# schematic.net
KiCad netlist of a schematic drawn in EAGLE
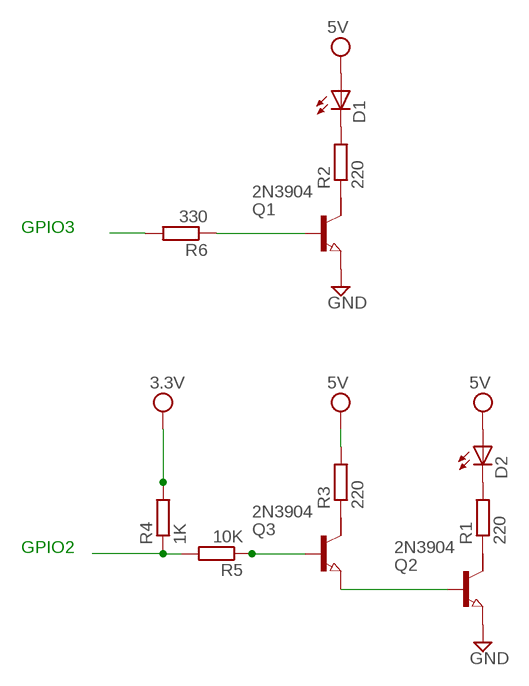
[diagram p0: schematic, sheet 1]

(export (version "E")
  (design (tool "Eeschema 10.0.6"))
  (components
    (comp (ref "D1")
      (value "LED")
      (footprint "eagle-import:SMARTLED-TTW")
      (libsource (lib "eagle-import") (part "LED"))
    )
    (comp (ref "D2")
      (value "LED")
      (footprint "eagle-import:SMARTLED-TTW")
      (libsource (lib "eagle-import") (part "LED"))
    )
    (comp (ref "Q1")
      (value "2N3904")
      (footprint "eagle-import:SOT89")
      (libsource (lib "eagle-import") (part "NPN-TRANSISTIOR-2COLSOT89"))
    )
    (comp (ref "Q2")
      (value "2N3904")
      (footprint "eagle-import:SOT89")
      (libsource (lib "eagle-import") (part "NPN-TRANSISTIOR-2COLSOT89"))
    )
    (comp (ref "Q3")
      (value "2N3904")
      (footprint "eagle-import:SOT89")
      (libsource (lib "eagle-import") (part "NPN-TRANSISTIOR-2COLSOT89"))
    )
    (comp (ref "R1")
      (value "220")
      (footprint "eagle-import:R0805")
      (libsource (lib "eagle-import") (part "R"))
    )
    (comp (ref "R2")
      (value "220")
      (footprint "eagle-import:R0805")
      (libsource (lib "eagle-import") (part "R"))
    )
    (comp (ref "R3")
      (value "220")
      (footprint "eagle-import:R0805")
      (libsource (lib "eagle-import") (part "R"))
    )
    (comp (ref "R4")
      (value "1K")
      (footprint "eagle-import:R0805")
      (libsource (lib "eagle-import") (part "R"))
    )
    (comp (ref "R5")
      (value "10K")
      (footprint "eagle-import:R0805")
      (libsource (lib "eagle-import") (part "R"))
    )
    (comp (ref "R6")
      (value "330")
      (footprint "eagle-import:R0805")
      (libsource (lib "eagle-import") (part "R"))
    )
  )
  (nets
    (net (code "1") (name "3.3V") (class "Default")
      (node (ref "D1") (pin "A@1") (pinfunction "A_A@1") (pintype "passive"))
      (node (ref "D2") (pin "A@1") (pinfunction "A_A@1") (pintype "passive"))
      (node (ref "R3") (pin "2") (pinfunction "2_2") (pintype "passive"))
      (node (ref "R4") (pin "2") (pinfunction "2_2") (pintype "passive"))
    )
    (net (code "2") (name "GND") (class "Default")
      (node (ref "Q1") (pin "3") (pinfunction "E_3") (pintype "passive"))
      (node (ref "Q2") (pin "3") (pinfunction "E_3") (pintype "passive"))
    )
    (net (code "3") (name "Net-(D1-C)") (class "Default")
      (node (ref "D1") (pin "C@1") (pinfunction "C_C@1") (pintype "passive"))
      (node (ref "R2") (pin "2") (pinfunction "2_2") (pintype "passive"))
    )
    (net (code "4") (name "Net-(D2-C)") (class "Default")
      (node (ref "D2") (pin "C@1") (pinfunction "C_C@1") (pintype "passive"))
      (node (ref "R1") (pin "2") (pinfunction "2_2") (pintype "passive"))
    )
    (net (code "5") (name "Net-(Q1-B)") (class "Default")
      (node (ref "Q1") (pin "1") (pinfunction "B_1") (pintype "passive"))
      (node (ref "R6") (pin "1") (pinfunction "1_1") (pintype "passive"))
    )
    (net (code "6") (name "Net-(Q1-C)") (class "Default")
      (node (ref "Q1") (pin "2") (pinfunction "C_2") (pintype "passive"))
      (node (ref "R2") (pin "1") (pinfunction "1_1") (pintype "passive"))
    )
    (net (code "7") (name "Net-(Q2-B)") (class "Default")
      (node (ref "Q2") (pin "1") (pinfunction "B_1") (pintype "passive"))
      (node (ref "Q3") (pin "3") (pinfunction "E_3") (pintype "passive"))
    )
    (net (code "8") (name "Net-(Q2-C)") (class "Default")
      (node (ref "Q2") (pin "2") (pinfunction "C_2") (pintype "passive"))
      (node (ref "R1") (pin "1") (pinfunction "1_1") (pintype "passive"))
    )
    (net (code "9") (name "Net-(Q3-B)") (class "Default")
      (node (ref "Q3") (pin "1") (pinfunction "B_1") (pintype "passive"))
      (node (ref "R5") (pin "1") (pinfunction "1_1") (pintype "passive"))
    )
    (net (code "10") (name "Net-(Q3-C)") (class "Default")
      (node (ref "Q3") (pin "2") (pinfunction "C_2") (pintype "passive"))
      (node (ref "R3") (pin "1") (pinfunction "1_1") (pintype "passive"))
    )
    (net (code "11") (name "Net-(R4-Pad1)") (class "Default")
      (node (ref "R4") (pin "1") (pinfunction "1_1") (pintype "passive"))
      (node (ref "R5") (pin "2") (pinfunction "2_2") (pintype "passive"))
    )
    (net (code "12") (name "unconnected-(Q1-C{slash}-Pad2@1)") (class "Default")
      (node (ref "Q1") (pin "2@1") (pinfunction "C/_2@1") (pintype "passive"))
    )
    (net (code "13") (name "unconnected-(Q2-C{slash}-Pad2@1)") (class "Default")
      (node (ref "Q2") (pin "2@1") (pinfunction "C/_2@1") (pintype "passive"))
    )
    (net (code "14") (name "unconnected-(Q3-C{slash}-Pad2@1)") (class "Default")
      (node (ref "Q3") (pin "2@1") (pinfunction "C/_2@1") (pintype "passive"))
    )
    (net (code "15") (name "unconnected-(R6-Pad2)") (class "Default")
      (node (ref "R6") (pin "2") (pinfunction "2_2") (pintype "passive"))
    )
  )
)
